# top.net
KiCad netlist of a schematic drawn in Altium Designer
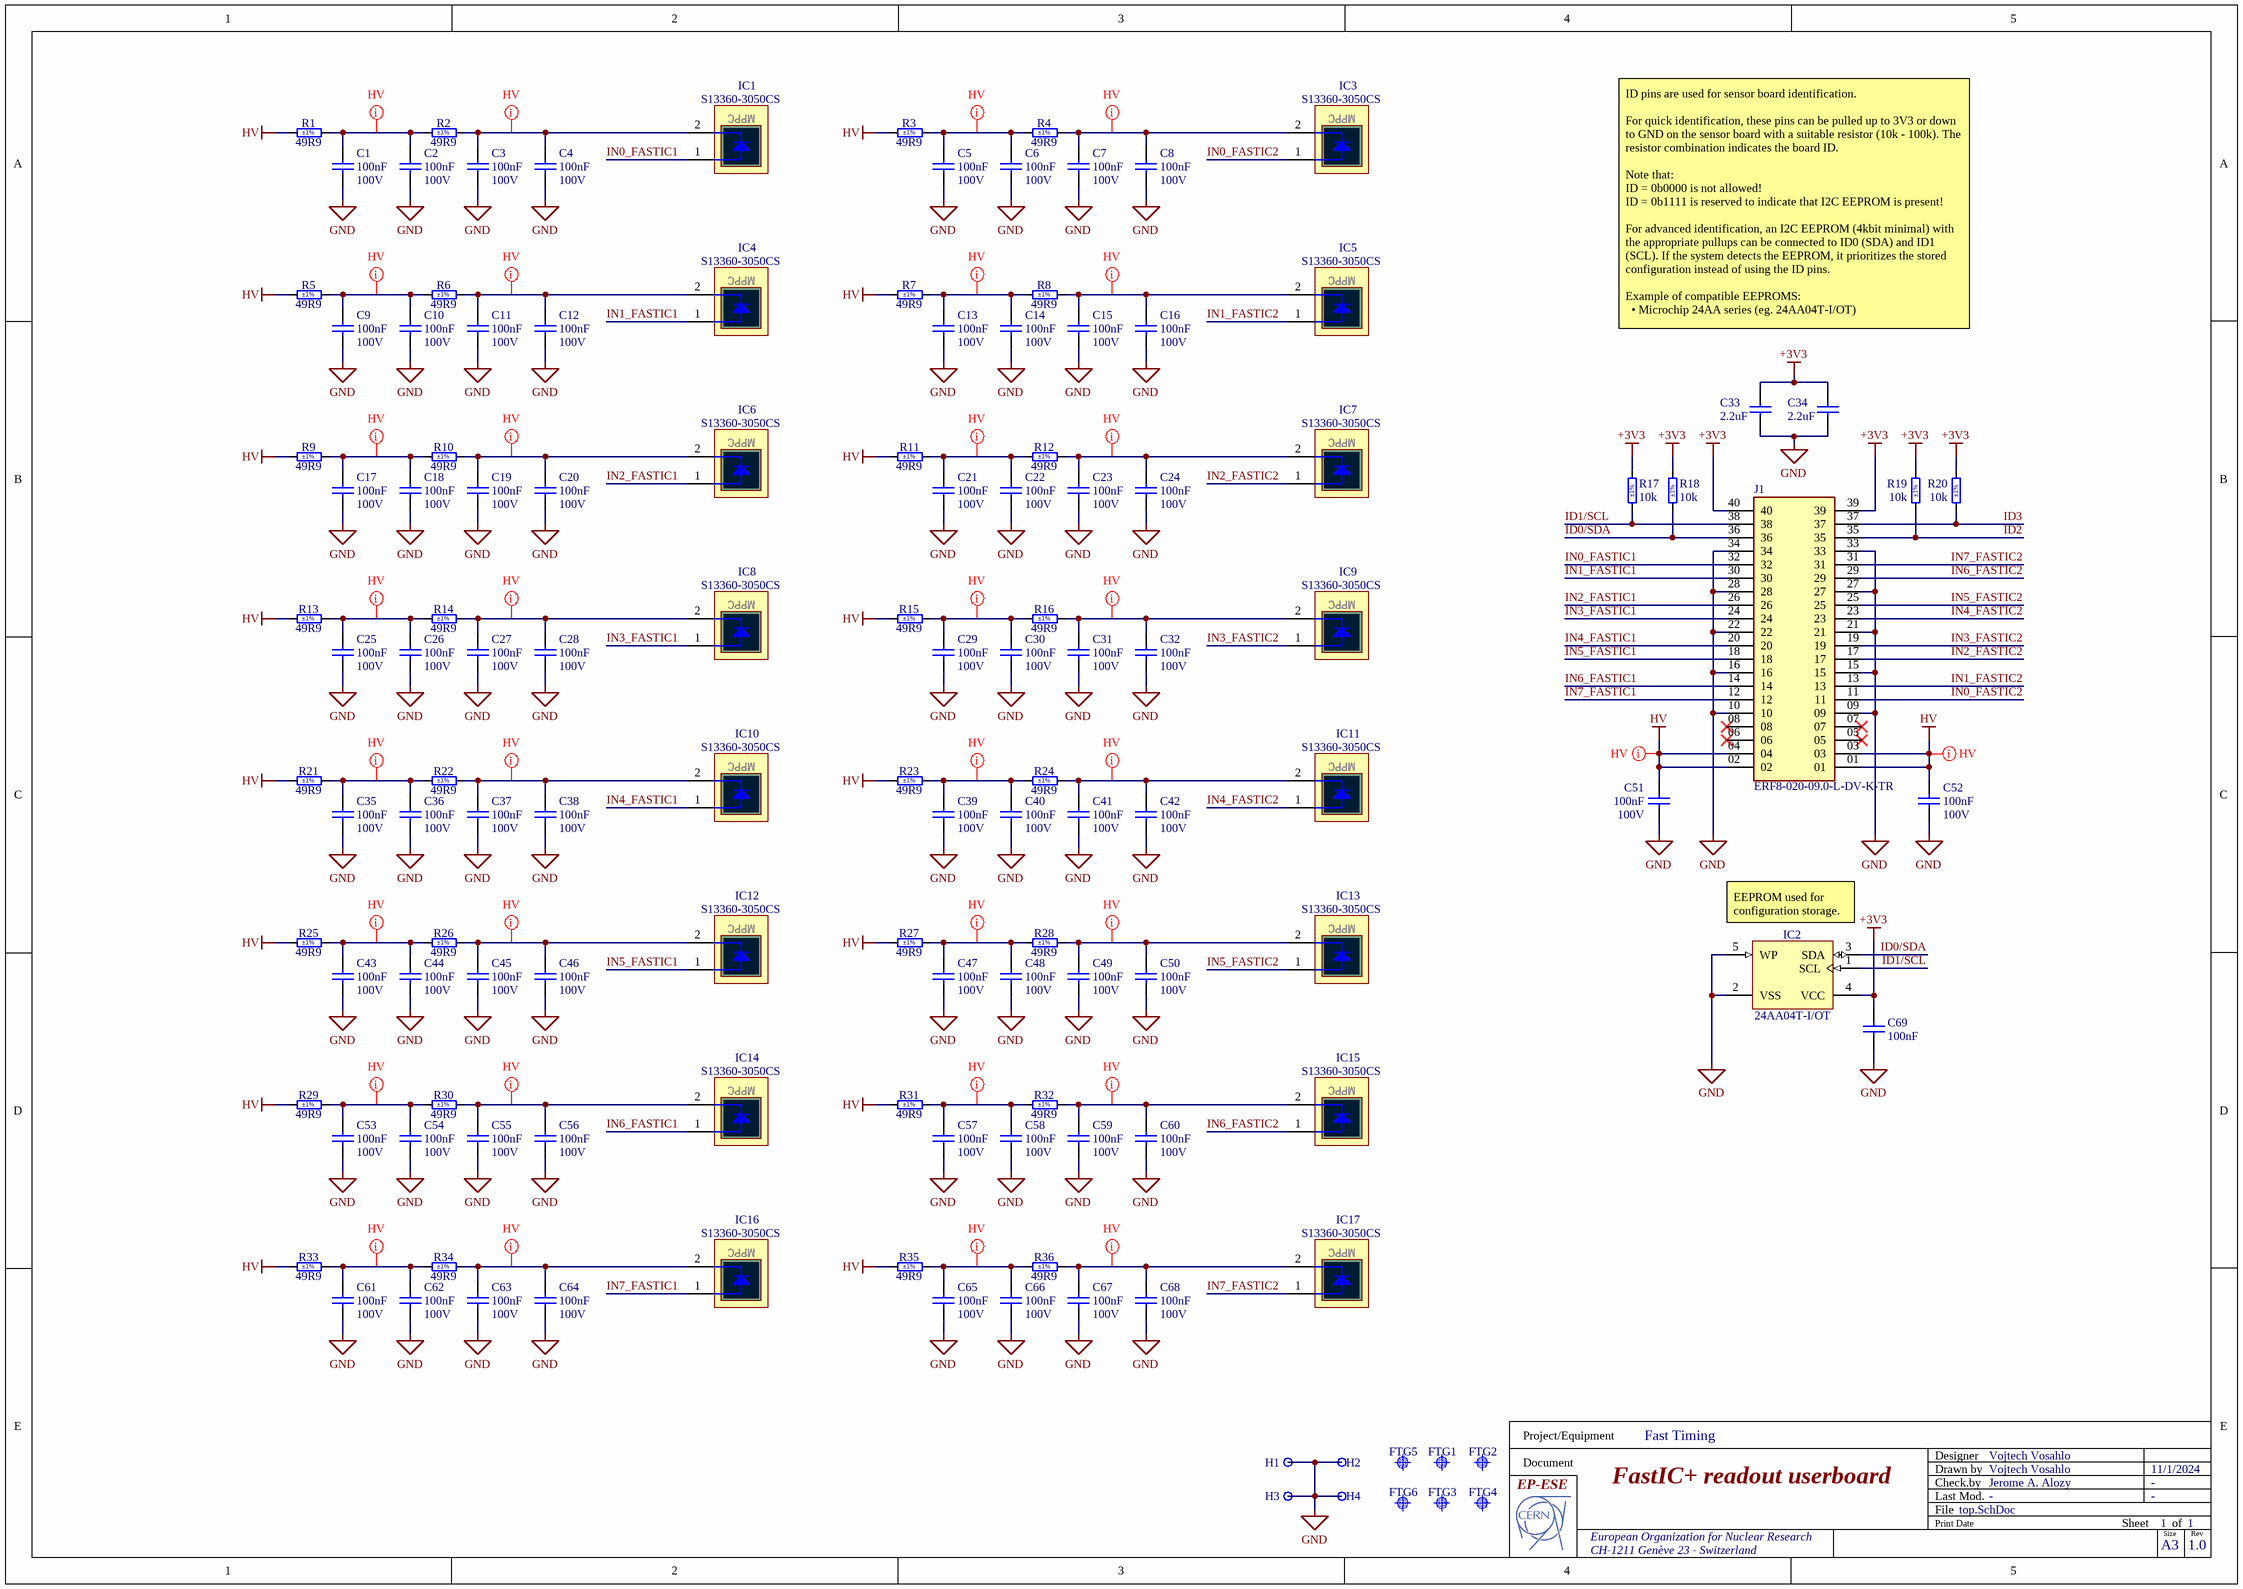
[diagram p0: top.SchDoc]

(export (version "E")
  (design (tool "Eeschema 10.0.6"))
  (components
    (comp (ref "C1")
      (value "100nF")
      (footprint "CAPC1608X90N")
      (description "Non-polarised capacitor")
      (fields
        (field (name "PART NUMBER") "CC0603_100NF_100V_10%_X7R")
        (field (name "VOLTAGE") "100V")
        (field (name "TOLERANCE") "±10%")
        (field (name "AUTHOR") "CERN DEM JLC")
      )
      (libsource (lib "Capacitors") (part "Capacitor - non polarized"))
    )
    (comp (ref "C2")
      (value "100nF")
      (footprint "CAPC1608X90N")
      (description "Non-polarised capacitor")
      (fields
        (field (name "PART NUMBER") "CC0603_100NF_100V_10%_X7R")
        (field (name "VOLTAGE") "100V")
        (field (name "TOLERANCE") "±10%")
        (field (name "AUTHOR") "CERN DEM JLC")
      )
      (libsource (lib "Capacitors") (part "Capacitor - non polarized"))
    )
    (comp (ref "C3")
      (value "100nF")
      (footprint "CAPC1608X90N")
      (description "Non-polarised capacitor")
      (fields
        (field (name "PART NUMBER") "CC0603_100NF_100V_10%_X7R")
        (field (name "VOLTAGE") "100V")
        (field (name "TOLERANCE") "±10%")
        (field (name "AUTHOR") "CERN DEM JLC")
      )
      (libsource (lib "Capacitors") (part "Capacitor - non polarized"))
    )
    (comp (ref "C4")
      (value "100nF")
      (footprint "CAPC1608X90N")
      (description "Non-polarised capacitor")
      (fields
        (field (name "PART NUMBER") "CC0603_100NF_100V_10%_X7R")
        (field (name "VOLTAGE") "100V")
        (field (name "TOLERANCE") "±10%")
        (field (name "AUTHOR") "CERN DEM JLC")
      )
      (libsource (lib "Capacitors") (part "Capacitor - non polarized"))
    )
    (comp (ref "C5")
      (value "100nF")
      (footprint "CAPC1608X90N")
      (description "Non-polarised capacitor")
      (fields
        (field (name "PART NUMBER") "CC0603_100NF_100V_10%_X7R")
        (field (name "VOLTAGE") "100V")
        (field (name "TOLERANCE") "±10%")
        (field (name "AUTHOR") "CERN DEM JLC")
      )
      (libsource (lib "Capacitors") (part "Capacitor - non polarized"))
    )
    (comp (ref "C6")
      (value "100nF")
      (footprint "CAPC1608X90N")
      (description "Non-polarised capacitor")
      (fields
        (field (name "PART NUMBER") "CC0603_100NF_100V_10%_X7R")
        (field (name "VOLTAGE") "100V")
        (field (name "TOLERANCE") "±10%")
        (field (name "AUTHOR") "CERN DEM JLC")
      )
      (libsource (lib "Capacitors") (part "Capacitor - non polarized"))
    )
    (comp (ref "C7")
      (value "100nF")
      (footprint "CAPC1608X90N")
      (description "Non-polarised capacitor")
      (fields
        (field (name "PART NUMBER") "CC0603_100NF_100V_10%_X7R")
        (field (name "VOLTAGE") "100V")
        (field (name "TOLERANCE") "±10%")
        (field (name "AUTHOR") "CERN DEM JLC")
      )
      (libsource (lib "Capacitors") (part "Capacitor - non polarized"))
    )
    (comp (ref "C8")
      (value "100nF")
      (footprint "CAPC1608X90N")
      (description "Non-polarised capacitor")
      (fields
        (field (name "PART NUMBER") "CC0603_100NF_100V_10%_X7R")
        (field (name "VOLTAGE") "100V")
        (field (name "TOLERANCE") "±10%")
        (field (name "AUTHOR") "CERN DEM JLC")
      )
      (libsource (lib "Capacitors") (part "Capacitor - non polarized"))
    )
    (comp (ref "C9")
      (value "100nF")
      (footprint "CAPC1608X90N")
      (description "Non-polarised capacitor")
      (fields
        (field (name "PART NUMBER") "CC0603_100NF_100V_10%_X7R")
        (field (name "VOLTAGE") "100V")
        (field (name "TOLERANCE") "±10%")
        (field (name "AUTHOR") "CERN DEM JLC")
      )
      (libsource (lib "Capacitors") (part "Capacitor - non polarized"))
    )
    (comp (ref "C10")
      (value "100nF")
      (footprint "CAPC1608X90N")
      (description "Non-polarised capacitor")
      (fields
        (field (name "PART NUMBER") "CC0603_100NF_100V_10%_X7R")
        (field (name "VOLTAGE") "100V")
        (field (name "TOLERANCE") "±10%")
        (field (name "AUTHOR") "CERN DEM JLC")
      )
      (libsource (lib "Capacitors") (part "Capacitor - non polarized"))
    )
    (comp (ref "C11")
      (value "100nF")
      (footprint "CAPC1608X90N")
      (description "Non-polarised capacitor")
      (fields
        (field (name "PART NUMBER") "CC0603_100NF_100V_10%_X7R")
        (field (name "VOLTAGE") "100V")
        (field (name "TOLERANCE") "±10%")
        (field (name "AUTHOR") "CERN DEM JLC")
      )
      (libsource (lib "Capacitors") (part "Capacitor - non polarized"))
    )
    (comp (ref "C12")
      (value "100nF")
      (footprint "CAPC1608X90N")
      (description "Non-polarised capacitor")
      (fields
        (field (name "PART NUMBER") "CC0603_100NF_100V_10%_X7R")
        (field (name "VOLTAGE") "100V")
        (field (name "TOLERANCE") "±10%")
        (field (name "AUTHOR") "CERN DEM JLC")
      )
      (libsource (lib "Capacitors") (part "Capacitor - non polarized"))
    )
    (comp (ref "C13")
      (value "100nF")
      (footprint "CAPC1608X90N")
      (description "Non-polarised capacitor")
      (fields
        (field (name "PART NUMBER") "CC0603_100NF_100V_10%_X7R")
        (field (name "VOLTAGE") "100V")
        (field (name "TOLERANCE") "±10%")
        (field (name "AUTHOR") "CERN DEM JLC")
      )
      (libsource (lib "Capacitors") (part "Capacitor - non polarized"))
    )
    (comp (ref "C14")
      (value "100nF")
      (footprint "CAPC1608X90N")
      (description "Non-polarised capacitor")
      (fields
        (field (name "PART NUMBER") "CC0603_100NF_100V_10%_X7R")
        (field (name "VOLTAGE") "100V")
        (field (name "TOLERANCE") "±10%")
        (field (name "AUTHOR") "CERN DEM JLC")
      )
      (libsource (lib "Capacitors") (part "Capacitor - non polarized"))
    )
    (comp (ref "C15")
      (value "100nF")
      (footprint "CAPC1608X90N")
      (description "Non-polarised capacitor")
      (fields
        (field (name "PART NUMBER") "CC0603_100NF_100V_10%_X7R")
        (field (name "VOLTAGE") "100V")
        (field (name "TOLERANCE") "±10%")
        (field (name "AUTHOR") "CERN DEM JLC")
      )
      (libsource (lib "Capacitors") (part "Capacitor - non polarized"))
    )
    (comp (ref "C16")
      (value "100nF")
      (footprint "CAPC1608X90N")
      (description "Non-polarised capacitor")
      (fields
        (field (name "PART NUMBER") "CC0603_100NF_100V_10%_X7R")
        (field (name "VOLTAGE") "100V")
        (field (name "TOLERANCE") "±10%")
        (field (name "AUTHOR") "CERN DEM JLC")
      )
      (libsource (lib "Capacitors") (part "Capacitor - non polarized"))
    )
    (comp (ref "C17")
      (value "100nF")
      (footprint "CAPC1608X90N")
      (description "Non-polarised capacitor")
      (fields
        (field (name "PART NUMBER") "CC0603_100NF_100V_10%_X7R")
        (field (name "VOLTAGE") "100V")
        (field (name "TOLERANCE") "±10%")
        (field (name "AUTHOR") "CERN DEM JLC")
      )
      (libsource (lib "Capacitors") (part "Capacitor - non polarized"))
    )
    (comp (ref "C18")
      (value "100nF")
      (footprint "CAPC1608X90N")
      (description "Non-polarised capacitor")
      (fields
        (field (name "PART NUMBER") "CC0603_100NF_100V_10%_X7R")
        (field (name "VOLTAGE") "100V")
        (field (name "TOLERANCE") "±10%")
        (field (name "AUTHOR") "CERN DEM JLC")
      )
      (libsource (lib "Capacitors") (part "Capacitor - non polarized"))
    )
    (comp (ref "C19")
      (value "100nF")
      (footprint "CAPC1608X90N")
      (description "Non-polarised capacitor")
      (fields
        (field (name "PART NUMBER") "CC0603_100NF_100V_10%_X7R")
        (field (name "VOLTAGE") "100V")
        (field (name "TOLERANCE") "±10%")
        (field (name "AUTHOR") "CERN DEM JLC")
      )
      (libsource (lib "Capacitors") (part "Capacitor - non polarized"))
    )
    (comp (ref "C20")
      (value "100nF")
      (footprint "CAPC1608X90N")
      (description "Non-polarised capacitor")
      (fields
        (field (name "PART NUMBER") "CC0603_100NF_100V_10%_X7R")
        (field (name "VOLTAGE") "100V")
        (field (name "TOLERANCE") "±10%")
        (field (name "AUTHOR") "CERN DEM JLC")
      )
      (libsource (lib "Capacitors") (part "Capacitor - non polarized"))
    )
    (comp (ref "C21")
      (value "100nF")
      (footprint "CAPC1608X90N")
      (description "Non-polarised capacitor")
      (fields
        (field (name "PART NUMBER") "CC0603_100NF_100V_10%_X7R")
        (field (name "VOLTAGE") "100V")
        (field (name "TOLERANCE") "±10%")
        (field (name "AUTHOR") "CERN DEM JLC")
      )
      (libsource (lib "Capacitors") (part "Capacitor - non polarized"))
    )
    (comp (ref "C22")
      (value "100nF")
      (footprint "CAPC1608X90N")
      (description "Non-polarised capacitor")
      (fields
        (field (name "PART NUMBER") "CC0603_100NF_100V_10%_X7R")
        (field (name "VOLTAGE") "100V")
        (field (name "TOLERANCE") "±10%")
        (field (name "AUTHOR") "CERN DEM JLC")
      )
      (libsource (lib "Capacitors") (part "Capacitor - non polarized"))
    )
    (comp (ref "C23")
      (value "100nF")
      (footprint "CAPC1608X90N")
      (description "Non-polarised capacitor")
      (fields
        (field (name "PART NUMBER") "CC0603_100NF_100V_10%_X7R")
        (field (name "VOLTAGE") "100V")
        (field (name "TOLERANCE") "±10%")
        (field (name "AUTHOR") "CERN DEM JLC")
      )
      (libsource (lib "Capacitors") (part "Capacitor - non polarized"))
    )
    (comp (ref "C24")
      (value "100nF")
      (footprint "CAPC1608X90N")
      (description "Non-polarised capacitor")
      (fields
        (field (name "PART NUMBER") "CC0603_100NF_100V_10%_X7R")
        (field (name "VOLTAGE") "100V")
        (field (name "TOLERANCE") "±10%")
        (field (name "AUTHOR") "CERN DEM JLC")
      )
      (libsource (lib "Capacitors") (part "Capacitor - non polarized"))
    )
    (comp (ref "C25")
      (value "100nF")
      (footprint "CAPC1608X90N")
      (description "Non-polarised capacitor")
      (fields
        (field (name "PART NUMBER") "CC0603_100NF_100V_10%_X7R")
        (field (name "VOLTAGE") "100V")
        (field (name "TOLERANCE") "±10%")
        (field (name "AUTHOR") "CERN DEM JLC")
      )
      (libsource (lib "Capacitors") (part "Capacitor - non polarized"))
    )
    (comp (ref "C26")
      (value "100nF")
      (footprint "CAPC1608X90N")
      (description "Non-polarised capacitor")
      (fields
        (field (name "PART NUMBER") "CC0603_100NF_100V_10%_X7R")
        (field (name "VOLTAGE") "100V")
        (field (name "TOLERANCE") "±10%")
        (field (name "AUTHOR") "CERN DEM JLC")
      )
      (libsource (lib "Capacitors") (part "Capacitor - non polarized"))
    )
    (comp (ref "C27")
      (value "100nF")
      (footprint "CAPC1608X90N")
      (description "Non-polarised capacitor")
      (fields
        (field (name "PART NUMBER") "CC0603_100NF_100V_10%_X7R")
        (field (name "VOLTAGE") "100V")
        (field (name "TOLERANCE") "±10%")
        (field (name "AUTHOR") "CERN DEM JLC")
      )
      (libsource (lib "Capacitors") (part "Capacitor - non polarized"))
    )
    (comp (ref "C28")
      (value "100nF")
      (footprint "CAPC1608X90N")
      (description "Non-polarised capacitor")
      (fields
        (field (name "PART NUMBER") "CC0603_100NF_100V_10%_X7R")
        (field (name "VOLTAGE") "100V")
        (field (name "TOLERANCE") "±10%")
        (field (name "AUTHOR") "CERN DEM JLC")
      )
      (libsource (lib "Capacitors") (part "Capacitor - non polarized"))
    )
    (comp (ref "C29")
      (value "100nF")
      (footprint "CAPC1608X90N")
      (description "Non-polarised capacitor")
      (fields
        (field (name "PART NUMBER") "CC0603_100NF_100V_10%_X7R")
        (field (name "VOLTAGE") "100V")
        (field (name "TOLERANCE") "±10%")
        (field (name "AUTHOR") "CERN DEM JLC")
      )
      (libsource (lib "Capacitors") (part "Capacitor - non polarized"))
    )
    (comp (ref "C30")
      (value "100nF")
      (footprint "CAPC1608X90N")
      (description "Non-polarised capacitor")
      (fields
        (field (name "PART NUMBER") "CC0603_100NF_100V_10%_X7R")
        (field (name "VOLTAGE") "100V")
        (field (name "TOLERANCE") "±10%")
        (field (name "AUTHOR") "CERN DEM JLC")
      )
      (libsource (lib "Capacitors") (part "Capacitor - non polarized"))
    )
    (comp (ref "C31")
      (value "100nF")
      (footprint "CAPC1608X90N")
      (description "Non-polarised capacitor")
      (fields
        (field (name "PART NUMBER") "CC0603_100NF_100V_10%_X7R")
        (field (name "VOLTAGE") "100V")
        (field (name "TOLERANCE") "±10%")
        (field (name "AUTHOR") "CERN DEM JLC")
      )
      (libsource (lib "Capacitors") (part "Capacitor - non polarized"))
    )
    (comp (ref "C32")
      (value "100nF")
      (footprint "CAPC1608X90N")
      (description "Non-polarised capacitor")
      (fields
        (field (name "PART NUMBER") "CC0603_100NF_100V_10%_X7R")
        (field (name "VOLTAGE") "100V")
        (field (name "TOLERANCE") "±10%")
        (field (name "AUTHOR") "CERN DEM JLC")
      )
      (libsource (lib "Capacitors") (part "Capacitor - non polarized"))
    )
    (comp (ref "C33")
      (value "2.2uF")
      (footprint "CAPC1608X90N")
      (description "Non-polarised capacitor")
      (fields
        (field (name "PART NUMBER") "CC0603_2.2UF_10V_20%_X7R")
        (field (name "VOLTAGE") "10V")
        (field (name "AUTHOR") "CERN DEM JLC")
      )
      (libsource (lib "Capacitors") (part "Capacitor - non polarized"))
    )
    (comp (ref "C34")
      (value "2.2uF")
      (footprint "CAPC1608X90N")
      (description "Non-polarised capacitor")
      (fields
        (field (name "PART NUMBER") "CC0603_2.2UF_10V_20%_X7R")
        (field (name "VOLTAGE") "10V")
        (field (name "AUTHOR") "CERN DEM JLC")
      )
      (libsource (lib "Capacitors") (part "Capacitor - non polarized"))
    )
    (comp (ref "C35")
      (value "100nF")
      (footprint "CAPC1608X90N")
      (description "Non-polarised capacitor")
      (fields
        (field (name "PART NUMBER") "CC0603_100NF_100V_10%_X7R")
        (field (name "VOLTAGE") "100V")
        (field (name "TOLERANCE") "±10%")
        (field (name "AUTHOR") "CERN DEM JLC")
      )
      (libsource (lib "Capacitors") (part "Capacitor - non polarized"))
    )
    (comp (ref "C36")
      (value "100nF")
      (footprint "CAPC1608X90N")
      (description "Non-polarised capacitor")
      (fields
        (field (name "PART NUMBER") "CC0603_100NF_100V_10%_X7R")
        (field (name "VOLTAGE") "100V")
        (field (name "TOLERANCE") "±10%")
        (field (name "AUTHOR") "CERN DEM JLC")
      )
      (libsource (lib "Capacitors") (part "Capacitor - non polarized"))
    )
    (comp (ref "C37")
      (value "100nF")
      (footprint "CAPC1608X90N")
      (description "Non-polarised capacitor")
      (fields
        (field (name "PART NUMBER") "CC0603_100NF_100V_10%_X7R")
        (field (name "VOLTAGE") "100V")
        (field (name "TOLERANCE") "±10%")
        (field (name "AUTHOR") "CERN DEM JLC")
      )
      (libsource (lib "Capacitors") (part "Capacitor - non polarized"))
    )
    (comp (ref "C38")
      (value "100nF")
      (footprint "CAPC1608X90N")
      (description "Non-polarised capacitor")
      (fields
        (field (name "PART NUMBER") "CC0603_100NF_100V_10%_X7R")
        (field (name "VOLTAGE") "100V")
        (field (name "TOLERANCE") "±10%")
        (field (name "AUTHOR") "CERN DEM JLC")
      )
      (libsource (lib "Capacitors") (part "Capacitor - non polarized"))
    )
    (comp (ref "C39")
      (value "100nF")
      (footprint "CAPC1608X90N")
      (description "Non-polarised capacitor")
      (fields
        (field (name "PART NUMBER") "CC0603_100NF_100V_10%_X7R")
        (field (name "VOLTAGE") "100V")
        (field (name "TOLERANCE") "±10%")
        (field (name "AUTHOR") "CERN DEM JLC")
      )
      (libsource (lib "Capacitors") (part "Capacitor - non polarized"))
    )
    (comp (ref "C40")
      (value "100nF")
      (footprint "CAPC1608X90N")
      (description "Non-polarised capacitor")
      (fields
        (field (name "PART NUMBER") "CC0603_100NF_100V_10%_X7R")
        (field (name "VOLTAGE") "100V")
        (field (name "TOLERANCE") "±10%")
        (field (name "AUTHOR") "CERN DEM JLC")
      )
      (libsource (lib "Capacitors") (part "Capacitor - non polarized"))
    )
    (comp (ref "C41")
      (value "100nF")
      (footprint "CAPC1608X90N")
      (description "Non-polarised capacitor")
      (fields
        (field (name "PART NUMBER") "CC0603_100NF_100V_10%_X7R")
        (field (name "VOLTAGE") "100V")
        (field (name "TOLERANCE") "±10%")
        (field (name "AUTHOR") "CERN DEM JLC")
      )
      (libsource (lib "Capacitors") (part "Capacitor - non polarized"))
    )
    (comp (ref "C42")
      (value "100nF")
      (footprint "CAPC1608X90N")
      (description "Non-polarised capacitor")
      (fields
        (field (name "PART NUMBER") "CC0603_100NF_100V_10%_X7R")
        (field (name "VOLTAGE") "100V")
        (field (name "TOLERANCE") "±10%")
        (field (name "AUTHOR") "CERN DEM JLC")
      )
      (libsource (lib "Capacitors") (part "Capacitor - non polarized"))
    )
    (comp (ref "C43")
      (value "100nF")
      (footprint "CAPC1608X90N")
      (description "Non-polarised capacitor")
      (fields
        (field (name "PART NUMBER") "CC0603_100NF_100V_10%_X7R")
        (field (name "VOLTAGE") "100V")
        (field (name "TOLERANCE") "±10%")
        (field (name "AUTHOR") "CERN DEM JLC")
      )
      (libsource (lib "Capacitors") (part "Capacitor - non polarized"))
    )
    (comp (ref "C44")
      (value "100nF")
      (footprint "CAPC1608X90N")
      (description "Non-polarised capacitor")
      (fields
        (field (name "PART NUMBER") "CC0603_100NF_100V_10%_X7R")
        (field (name "VOLTAGE") "100V")
        (field (name "TOLERANCE") "±10%")
        (field (name "AUTHOR") "CERN DEM JLC")
      )
      (libsource (lib "Capacitors") (part "Capacitor - non polarized"))
    )
    (comp (ref "C45")
      (value "100nF")
      (footprint "CAPC1608X90N")
      (description "Non-polarised capacitor")
      (fields
        (field (name "PART NUMBER") "CC0603_100NF_100V_10%_X7R")
        (field (name "VOLTAGE") "100V")
        (field (name "TOLERANCE") "±10%")
        (field (name "AUTHOR") "CERN DEM JLC")
      )
      (libsource (lib "Capacitors") (part "Capacitor - non polarized"))
    )
    (comp (ref "C46")
      (value "100nF")
      (footprint "CAPC1608X90N")
      (description "Non-polarised capacitor")
      (fields
        (field (name "PART NUMBER") "CC0603_100NF_100V_10%_X7R")
        (field (name "VOLTAGE") "100V")
        (field (name "TOLERANCE") "±10%")
        (field (name "AUTHOR") "CERN DEM JLC")
      )
      (libsource (lib "Capacitors") (part "Capacitor - non polarized"))
    )
    (comp (ref "C47")
      (value "100nF")
      (footprint "CAPC1608X90N")
      (description "Non-polarised capacitor")
      (fields
        (field (name "PART NUMBER") "CC0603_100NF_100V_10%_X7R")
        (field (name "VOLTAGE") "100V")
        (field (name "TOLERANCE") "±10%")
        (field (name "AUTHOR") "CERN DEM JLC")
      )
      (libsource (lib "Capacitors") (part "Capacitor - non polarized"))
    )
    (comp (ref "C48")
      (value "100nF")
      (footprint "CAPC1608X90N")
      (description "Non-polarised capacitor")
      (fields
        (field (name "PART NUMBER") "CC0603_100NF_100V_10%_X7R")
        (field (name "VOLTAGE") "100V")
        (field (name "TOLERANCE") "±10%")
        (field (name "AUTHOR") "CERN DEM JLC")
      )
      (libsource (lib "Capacitors") (part "Capacitor - non polarized"))
    )
    (comp (ref "C49")
      (value "100nF")
      (footprint "CAPC1608X90N")
      (description "Non-polarised capacitor")
      (fields
        (field (name "PART NUMBER") "CC0603_100NF_100V_10%_X7R")
        (field (name "VOLTAGE") "100V")
        (field (name "TOLERANCE") "±10%")
        (field (name "AUTHOR") "CERN DEM JLC")
      )
      (libsource (lib "Capacitors") (part "Capacitor - non polarized"))
    )
    (comp (ref "C50")
      (value "100nF")
      (footprint "CAPC1608X90N")
      (description "Non-polarised capacitor")
      (fields
        (field (name "PART NUMBER") "CC0603_100NF_100V_10%_X7R")
        (field (name "VOLTAGE") "100V")
        (field (name "TOLERANCE") "±10%")
        (field (name "AUTHOR") "CERN DEM JLC")
      )
      (libsource (lib "Capacitors") (part "Capacitor - non polarized"))
    )
    (comp (ref "C51")
      (value "100nF")
      (footprint "CAPC1608X90N")
      (description "Non-polarised capacitor")
      (fields
        (field (name "PART NUMBER") "CC0603_100NF_100V_10%_X7R")
        (field (name "VOLTAGE") "100V")
        (field (name "TOLERANCE") "±10%")
        (field (name "AUTHOR") "CERN DEM JLC")
      )
      (libsource (lib "Capacitors") (part "Capacitor - non polarized"))
    )
    (comp (ref "C52")
      (value "100nF")
      (footprint "CAPC1608X90N")
      (description "Non-polarised capacitor")
      (fields
        (field (name "PART NUMBER") "CC0603_100NF_100V_10%_X7R")
        (field (name "VOLTAGE") "100V")
        (field (name "TOLERANCE") "±10%")
        (field (name "AUTHOR") "CERN DEM JLC")
      )
      (libsource (lib "Capacitors") (part "Capacitor - non polarized"))
    )
    (comp (ref "C53")
      (value "100nF")
      (footprint "CAPC1608X90N")
      (description "Non-polarised capacitor")
      (fields
        (field (name "PART NUMBER") "CC0603_100NF_100V_10%_X7R")
        (field (name "VOLTAGE") "100V")
        (field (name "TOLERANCE") "±10%")
        (field (name "AUTHOR") "CERN DEM JLC")
      )
      (libsource (lib "Capacitors") (part "Capacitor - non polarized"))
    )
    (comp (ref "C54")
      (value "100nF")
      (footprint "CAPC1608X90N")
      (description "Non-polarised capacitor")
      (fields
        (field (name "PART NUMBER") "CC0603_100NF_100V_10%_X7R")
        (field (name "VOLTAGE") "100V")
        (field (name "TOLERANCE") "±10%")
        (field (name "AUTHOR") "CERN DEM JLC")
      )
      (libsource (lib "Capacitors") (part "Capacitor - non polarized"))
    )
    (comp (ref "C55")
      (value "100nF")
      (footprint "CAPC1608X90N")
      (description "Non-polarised capacitor")
      (fields
        (field (name "PART NUMBER") "CC0603_100NF_100V_10%_X7R")
        (field (name "VOLTAGE") "100V")
        (field (name "TOLERANCE") "±10%")
        (field (name "AUTHOR") "CERN DEM JLC")
      )
      (libsource (lib "Capacitors") (part "Capacitor - non polarized"))
    )
    (comp (ref "C56")
      (value "100nF")
      (footprint "CAPC1608X90N")
      (description "Non-polarised capacitor")
      (fields
        (field (name "PART NUMBER") "CC0603_100NF_100V_10%_X7R")
        (field (name "VOLTAGE") "100V")
        (field (name "TOLERANCE") "±10%")
        (field (name "AUTHOR") "CERN DEM JLC")
      )
      (libsource (lib "Capacitors") (part "Capacitor - non polarized"))
    )
    (comp (ref "C57")
      (value "100nF")
      (footprint "CAPC1608X90N")
      (description "Non-polarised capacitor")
      (fields
        (field (name "PART NUMBER") "CC0603_100NF_100V_10%_X7R")
        (field (name "VOLTAGE") "100V")
        (field (name "TOLERANCE") "±10%")
        (field (name "AUTHOR") "CERN DEM JLC")
      )
      (libsource (lib "Capacitors") (part "Capacitor - non polarized"))
    )
    (comp (ref "C58")
      (value "100nF")
      (footprint "CAPC1608X90N")
      (description "Non-polarised capacitor")
      (fields
        (field (name "PART NUMBER") "CC0603_100NF_100V_10%_X7R")
        (field (name "VOLTAGE") "100V")
        (field (name "TOLERANCE") "±10%")
        (field (name "AUTHOR") "CERN DEM JLC")
      )
      (libsource (lib "Capacitors") (part "Capacitor - non polarized"))
    )
    (comp (ref "C59")
      (value "100nF")
      (footprint "CAPC1608X90N")
      (description "Non-polarised capacitor")
      (fields
        (field (name "PART NUMBER") "CC0603_100NF_100V_10%_X7R")
        (field (name "VOLTAGE") "100V")
        (field (name "TOLERANCE") "±10%")
        (field (name "AUTHOR") "CERN DEM JLC")
      )
      (libsource (lib "Capacitors") (part "Capacitor - non polarized"))
    )
    (comp (ref "C60")
      (value "100nF")
      (footprint "CAPC1608X90N")
      (description "Non-polarised capacitor")
      (fields
        (field (name "PART NUMBER") "CC0603_100NF_100V_10%_X7R")
        (field (name "VOLTAGE") "100V")
        (field (name "TOLERANCE") "±10%")
        (field (name "AUTHOR") "CERN DEM JLC")
      )
      (libsource (lib "Capacitors") (part "Capacitor - non polarized"))
    )
    (comp (ref "C61")
      (value "100nF")
      (footprint "CAPC1608X90N")
      (description "Non-polarised capacitor")
      (fields
        (field (name "PART NUMBER") "CC0603_100NF_100V_10%_X7R")
        (field (name "VOLTAGE") "100V")
        (field (name "TOLERANCE") "±10%")
        (field (name "AUTHOR") "CERN DEM JLC")
      )
      (libsource (lib "Capacitors") (part "Capacitor - non polarized"))
    )
    (comp (ref "C62")
      (value "100nF")
      (footprint "CAPC1608X90N")
      (description "Non-polarised capacitor")
      (fields
        (field (name "PART NUMBER") "CC0603_100NF_100V_10%_X7R")
        (field (name "VOLTAGE") "100V")
        (field (name "TOLERANCE") "±10%")
        (field (name "AUTHOR") "CERN DEM JLC")
      )
      (libsource (lib "Capacitors") (part "Capacitor - non polarized"))
    )
    (comp (ref "C63")
      (value "100nF")
      (footprint "CAPC1608X90N")
      (description "Non-polarised capacitor")
      (fields
        (field (name "PART NUMBER") "CC0603_100NF_100V_10%_X7R")
        (field (name "VOLTAGE") "100V")
        (field (name "TOLERANCE") "±10%")
        (field (name "AUTHOR") "CERN DEM JLC")
      )
      (libsource (lib "Capacitors") (part "Capacitor - non polarized"))
    )
    (comp (ref "C64")
      (value "100nF")
      (footprint "CAPC1608X90N")
      (description "Non-polarised capacitor")
      (fields
        (field (name "PART NUMBER") "CC0603_100NF_100V_10%_X7R")
        (field (name "VOLTAGE") "100V")
        (field (name "TOLERANCE") "±10%")
        (field (name "AUTHOR") "CERN DEM JLC")
      )
      (libsource (lib "Capacitors") (part "Capacitor - non polarized"))
    )
    (comp (ref "C65")
      (value "100nF")
      (footprint "CAPC1608X90N")
      (description "Non-polarised capacitor")
      (fields
        (field (name "PART NUMBER") "CC0603_100NF_100V_10%_X7R")
        (field (name "VOLTAGE") "100V")
        (field (name "TOLERANCE") "±10%")
        (field (name "AUTHOR") "CERN DEM JLC")
      )
      (libsource (lib "Capacitors") (part "Capacitor - non polarized"))
    )
    (comp (ref "C66")
      (value "100nF")
      (footprint "CAPC1608X90N")
      (description "Non-polarised capacitor")
      (fields
        (field (name "PART NUMBER") "CC0603_100NF_100V_10%_X7R")
        (field (name "VOLTAGE") "100V")
        (field (name "TOLERANCE") "±10%")
        (field (name "AUTHOR") "CERN DEM JLC")
      )
      (libsource (lib "Capacitors") (part "Capacitor - non polarized"))
    )
    (comp (ref "C67")
      (value "100nF")
      (footprint "CAPC1608X90N")
      (description "Non-polarised capacitor")
      (fields
        (field (name "PART NUMBER") "CC0603_100NF_100V_10%_X7R")
        (field (name "VOLTAGE") "100V")
        (field (name "TOLERANCE") "±10%")
        (field (name "AUTHOR") "CERN DEM JLC")
      )
      (libsource (lib "Capacitors") (part "Capacitor - non polarized"))
    )
    (comp (ref "C68")
      (value "100nF")
      (footprint "CAPC1608X90N")
      (description "Non-polarised capacitor")
      (fields
        (field (name "PART NUMBER") "CC0603_100NF_100V_10%_X7R")
        (field (name "VOLTAGE") "100V")
        (field (name "TOLERANCE") "±10%")
        (field (name "AUTHOR") "CERN DEM JLC")
      )
      (libsource (lib "Capacitors") (part "Capacitor - non polarized"))
    )
    (comp (ref "C69")
      (value "100nF")
      (footprint "CAPC1608X90N")
      (description "Non-polarised capacitor")
      (fields
        (field (name "PART NUMBER") "CC0603_100NF_100V_10%_X7R")
        (field (name "VOLTAGE") "100V")
        (field (name "AUTHOR") "CERN DEM JLC")
      )
      (libsource (lib "Capacitors") (part "Capacitor - non polarized"))
    )
    (comp (ref "FTG1")
      (value "Use only in PCB")
      (footprint "FIDUCIAL_TOP_C100-200")
      (description "Fiducial Target")
      (fields (field (name "PART NUMBER") "FIDUCIAL_TARGET_C100-200") (field (name "AUTHOR") "CERN DEM JLC"))
      (libsource (lib "Eletro-mechanical") (part "Fiducial Target"))
    )
    (comp (ref "FTG2")
      (value "Use only in PCB")
      (footprint "FIDUCIAL_TOP_C100-200")
      (description "Fiducial Target")
      (fields (field (name "PART NUMBER") "FIDUCIAL_TARGET_C100-200") (field (name "AUTHOR") "CERN DEM JLC"))
      (libsource (lib "Eletro-mechanical") (part "Fiducial Target"))
    )
    (comp (ref "FTG3")
      (value "Use only in PCB")
      (footprint "FIDUCIAL_TOP_C100-200")
      (description "Fiducial Target")
      (fields (field (name "PART NUMBER") "FIDUCIAL_TARGET_C100-200") (field (name "AUTHOR") "CERN DEM JLC"))
      (libsource (lib "Eletro-mechanical") (part "Fiducial Target"))
    )
    (comp (ref "FTG4")
      (value "Use only in PCB")
      (footprint "FIDUCIAL_TOP_C100-200")
      (description "Fiducial Target")
      (fields (field (name "PART NUMBER") "FIDUCIAL_TARGET_C100-200") (field (name "AUTHOR") "CERN DEM JLC"))
      (libsource (lib "Eletro-mechanical") (part "Fiducial Target"))
    )
    (comp (ref "FTG5")
      (value "Use only in PCB")
      (footprint "FIDUCIAL_TOP_C100-200")
      (description "Fiducial Target")
      (fields (field (name "PART NUMBER") "FIDUCIAL_TARGET_C100-200") (field (name "AUTHOR") "CERN DEM JLC"))
      (libsource (lib "Eletro-mechanical") (part "Fiducial Target"))
    )
    (comp (ref "FTG6")
      (value "Use only in PCB")
      (footprint "FIDUCIAL_TOP_C100-200")
      (description "Fiducial Target")
      (fields (field (name "PART NUMBER") "FIDUCIAL_TARGET_C100-200") (field (name "AUTHOR") "CERN DEM JLC"))
      (libsource (lib "Eletro-mechanical") (part "Fiducial Target"))
    )
    (comp (ref "H1")
      (value "Plated Hole")
      (footprint "MTG240_400")
      (description "Single Terminal Socket")
      (fields (field (name "PART NUMBER") "PLATED_HOLE2.4_PAD4.0") (field (name "AUTHOR") "CERN DEM JMW"))
      (libsource (lib "Eletro-mechanical") (part "Single Terminal Socket"))
    )
    (comp (ref "H2")
      (value "Plated Hole")
      (footprint "MTG240_400")
      (description "Single Terminal Socket")
      (fields (field (name "PART NUMBER") "PLATED_HOLE2.4_PAD4.0") (field (name "AUTHOR") "CERN DEM JMW"))
      (libsource (lib "Eletro-mechanical") (part "Single Terminal Socket"))
    )
    (comp (ref "H3")
      (value "Plated Hole")
      (footprint "MTG240_400")
      (description "Single Terminal Socket")
      (fields (field (name "PART NUMBER") "PLATED_HOLE2.4_PAD4.0") (field (name "AUTHOR") "CERN DEM JMW"))
      (libsource (lib "Eletro-mechanical") (part "Single Terminal Socket"))
    )
    (comp (ref "H4")
      (value "Plated Hole")
      (footprint "MTG240_400")
      (description "Single Terminal Socket")
      (fields (field (name "PART NUMBER") "PLATED_HOLE2.4_PAD4.0") (field (name "AUTHOR") "CERN DEM JMW"))
      (libsource (lib "Eletro-mechanical") (part "Single Terminal Socket"))
    )
    (comp (ref "IC1")
      (value "S13360-3050CS")
      (footprint "HAMAMATSU_S13360-3050CS")
      (description "Single Element MPPC (Multi-Pixel Photon Counter)")
      (fields (field (name "MANUFACTURER") "HAMAMATSU") (field (name "AUTHOR") "CERN DEM BC"))
      (libsource (lib "ICs And Semiconductors") (part "MPPC-Single Element"))
    )
    (comp (ref "IC2")
      (value "24AA04T-I/OT")
      (footprint "SOT95P280X145-5N")
      (description "1.7V-5.5V, 16K I2C Serial EEPROM")
      (fields
        (field (name "MANUFACTURER") "MICROCHIP TECHNOLOGY")
        (field (name "MANUFACTURER PART NUMBER") "24AA16T-E/OT")
        (field (name "AUTHOR") "CERN DEM BC")
      )
      (libsource (lib "ICs And Semiconductors") (part "24AA16T-X/OT"))
    )
    (comp (ref "IC3")
      (value "S13360-3050CS")
      (footprint "HAMAMATSU_S13360-3050CS")
      (description "Single Element MPPC (Multi-Pixel Photon Counter)")
      (fields (field (name "MANUFACTURER") "HAMAMATSU") (field (name "AUTHOR") "CERN DEM BC"))
      (libsource (lib "ICs And Semiconductors") (part "MPPC-Single Element"))
    )
    (comp (ref "IC4")
      (value "S13360-3050CS")
      (footprint "HAMAMATSU_S13360-3050CS")
      (description "Single Element MPPC (Multi-Pixel Photon Counter)")
      (fields (field (name "MANUFACTURER") "HAMAMATSU") (field (name "AUTHOR") "CERN DEM BC"))
      (libsource (lib "ICs And Semiconductors") (part "MPPC-Single Element"))
    )
    (comp (ref "IC5")
      (value "S13360-3050CS")
      (footprint "HAMAMATSU_S13360-3050CS")
      (description "Single Element MPPC (Multi-Pixel Photon Counter)")
      (fields (field (name "MANUFACTURER") "HAMAMATSU") (field (name "AUTHOR") "CERN DEM BC"))
      (libsource (lib "ICs And Semiconductors") (part "MPPC-Single Element"))
    )
    (comp (ref "IC6")
      (value "S13360-3050CS")
      (footprint "HAMAMATSU_S13360-3050CS")
      (description "Single Element MPPC (Multi-Pixel Photon Counter)")
      (fields (field (name "MANUFACTURER") "HAMAMATSU") (field (name "AUTHOR") "CERN DEM BC"))
      (libsource (lib "ICs And Semiconductors") (part "MPPC-Single Element"))
    )
    (comp (ref "IC7")
      (value "S13360-3050CS")
      (footprint "HAMAMATSU_S13360-3050CS")
      (description "Single Element MPPC (Multi-Pixel Photon Counter)")
      (fields (field (name "MANUFACTURER") "HAMAMATSU") (field (name "AUTHOR") "CERN DEM BC"))
      (libsource (lib "ICs And Semiconductors") (part "MPPC-Single Element"))
    )
    (comp (ref "IC8")
      (value "S13360-3050CS")
      (footprint "HAMAMATSU_S13360-3050CS")
      (description "Single Element MPPC (Multi-Pixel Photon Counter)")
      (fields (field (name "MANUFACTURER") "HAMAMATSU") (field (name "AUTHOR") "CERN DEM BC"))
      (libsource (lib "ICs And Semiconductors") (part "MPPC-Single Element"))
    )
    (comp (ref "IC9")
      (value "S13360-3050CS")
      (footprint "HAMAMATSU_S13360-3050CS")
      (description "Single Element MPPC (Multi-Pixel Photon Counter)")
      (fields (field (name "MANUFACTURER") "HAMAMATSU") (field (name "AUTHOR") "CERN DEM BC"))
      (libsource (lib "ICs And Semiconductors") (part "MPPC-Single Element"))
    )
    (comp (ref "IC10")
      (value "S13360-3050CS")
      (footprint "HAMAMATSU_S13360-3050CS")
      (description "Single Element MPPC (Multi-Pixel Photon Counter)")
      (fields (field (name "MANUFACTURER") "HAMAMATSU") (field (name "AUTHOR") "CERN DEM BC"))
      (libsource (lib "ICs And Semiconductors") (part "MPPC-Single Element"))
    )
    (comp (ref "IC11")
      (value "S13360-3050CS")
      (footprint "HAMAMATSU_S13360-3050CS")
      (description "Single Element MPPC (Multi-Pixel Photon Counter)")
      (fields (field (name "MANUFACTURER") "HAMAMATSU") (field (name "AUTHOR") "CERN DEM BC"))
      (libsource (lib "ICs And Semiconductors") (part "MPPC-Single Element"))
    )
    (comp (ref "IC12")
      (value "S13360-3050CS")
      (footprint "HAMAMATSU_S13360-3050CS")
      (description "Single Element MPPC (Multi-Pixel Photon Counter)")
      (fields (field (name "MANUFACTURER") "HAMAMATSU") (field (name "AUTHOR") "CERN DEM BC"))
      (libsource (lib "ICs And Semiconductors") (part "MPPC-Single Element"))
    )
    (comp (ref "IC13")
      (value "S13360-3050CS")
      (footprint "HAMAMATSU_S13360-3050CS")
      (description "Single Element MPPC (Multi-Pixel Photon Counter)")
      (fields (field (name "MANUFACTURER") "HAMAMATSU") (field (name "AUTHOR") "CERN DEM BC"))
      (libsource (lib "ICs And Semiconductors") (part "MPPC-Single Element"))
    )
    (comp (ref "IC14")
      (value "S13360-3050CS")
      (footprint "HAMAMATSU_S13360-3050CS")
      (description "Single Element MPPC (Multi-Pixel Photon Counter)")
      (fields (field (name "MANUFACTURER") "HAMAMATSU") (field (name "AUTHOR") "CERN DEM BC"))
      (libsource (lib "ICs And Semiconductors") (part "MPPC-Single Element"))
    )
    (comp (ref "IC15")
      (value "S13360-3050CS")
      (footprint "HAMAMATSU_S13360-3050CS")
      (description "Single Element MPPC (Multi-Pixel Photon Counter)")
      (fields (field (name "MANUFACTURER") "HAMAMATSU") (field (name "AUTHOR") "CERN DEM BC"))
      (libsource (lib "ICs And Semiconductors") (part "MPPC-Single Element"))
    )
    (comp (ref "IC16")
      (value "S13360-3050CS")
      (footprint "HAMAMATSU_S13360-3050CS")
      (description "Single Element MPPC (Multi-Pixel Photon Counter)")
      (fields (field (name "MANUFACTURER") "HAMAMATSU") (field (name "AUTHOR") "CERN DEM BC"))
      (libsource (lib "ICs And Semiconductors") (part "MPPC-Single Element"))
    )
    (comp (ref "IC17")
      (value "S13360-3050CS")
      (footprint "HAMAMATSU_S13360-3050CS")
      (description "Single Element MPPC (Multi-Pixel Photon Counter)")
      (fields (field (name "MANUFACTURER") "HAMAMATSU") (field (name "AUTHOR") "CERN DEM BC"))
      (libsource (lib "ICs And Semiconductors") (part "MPPC-Single Element"))
    )
    (comp (ref "J1")
      (value "ERF8-020-09.0-L-DV-K-TR")
      (footprint "SAMTEC_ERF8-020-09.0-L-DV-K-TR")
      (libsource (lib "ERF8-020-09.0-L-DV-K-TR") (part "ERF8-020-09.0-L-DV-K-TR"))
    )
    (comp (ref "R1")
      (value "49R9")
      (footprint "RESC1608X55N")
      (description "Resistor - 1%")
      (fields
        (field (name "TOLERANCE") "±1%")
        (field (name "PART NUMBER") "R0603_49R9_1%_0.1W_100PPM")
        (field (name "POWER") "0.1W")
        (field (name "AUTHOR") "CERN DEM JLC")
      )
      (libsource (lib "Resistors") (part "Resistor - 1%"))
    )
    (comp (ref "R2")
      (value "49R9")
      (footprint "RESC1608X55N")
      (description "Resistor - 1%")
      (fields
        (field (name "TOLERANCE") "±1%")
        (field (name "PART NUMBER") "R0603_49R9_1%_0.1W_100PPM")
        (field (name "POWER") "0.1W")
        (field (name "AUTHOR") "CERN DEM JLC")
      )
      (libsource (lib "Resistors") (part "Resistor - 1%"))
    )
    (comp (ref "R3")
      (value "49R9")
      (footprint "RESC1608X55N")
      (description "Resistor - 1%")
      (fields
        (field (name "TOLERANCE") "±1%")
        (field (name "PART NUMBER") "R0603_49R9_1%_0.1W_100PPM")
        (field (name "POWER") "0.1W")
        (field (name "AUTHOR") "CERN DEM JLC")
      )
      (libsource (lib "Resistors") (part "Resistor - 1%"))
    )
    (comp (ref "R4")
      (value "49R9")
      (footprint "RESC1608X55N")
      (description "Resistor - 1%")
      (fields
        (field (name "TOLERANCE") "±1%")
        (field (name "PART NUMBER") "R0603_49R9_1%_0.1W_100PPM")
        (field (name "POWER") "0.1W")
        (field (name "AUTHOR") "CERN DEM JLC")
      )
      (libsource (lib "Resistors") (part "Resistor - 1%"))
    )
    (comp (ref "R5")
      (value "49R9")
      (footprint "RESC1608X55N")
      (description "Resistor - 1%")
      (fields
        (field (name "TOLERANCE") "±1%")
        (field (name "PART NUMBER") "R0603_49R9_1%_0.1W_100PPM")
        (field (name "POWER") "0.1W")
        (field (name "AUTHOR") "CERN DEM JLC")
      )
      (libsource (lib "Resistors") (part "Resistor - 1%"))
    )
    (comp (ref "R6")
      (value "49R9")
      (footprint "RESC1608X55N")
      (description "Resistor - 1%")
      (fields
        (field (name "TOLERANCE") "±1%")
        (field (name "PART NUMBER") "R0603_49R9_1%_0.1W_100PPM")
        (field (name "POWER") "0.1W")
        (field (name "AUTHOR") "CERN DEM JLC")
      )
      (libsource (lib "Resistors") (part "Resistor - 1%"))
    )
    (comp (ref "R7")
      (value "49R9")
      (footprint "RESC1608X55N")
      (description "Resistor - 1%")
      (fields
        (field (name "TOLERANCE") "±1%")
        (field (name "PART NUMBER") "R0603_49R9_1%_0.1W_100PPM")
        (field (name "POWER") "0.1W")
        (field (name "AUTHOR") "CERN DEM JLC")
      )
      (libsource (lib "Resistors") (part "Resistor - 1%"))
    )
    (comp (ref "R8")
      (value "49R9")
      (footprint "RESC1608X55N")
      (description "Resistor - 1%")
      (fields
        (field (name "TOLERANCE") "±1%")
        (field (name "PART NUMBER") "R0603_49R9_1%_0.1W_100PPM")
        (field (name "POWER") "0.1W")
        (field (name "AUTHOR") "CERN DEM JLC")
      )
      (libsource (lib "Resistors") (part "Resistor - 1%"))
    )
    (comp (ref "R9")
      (value "49R9")
      (footprint "RESC1608X55N")
      (description "Resistor - 1%")
      (fields
        (field (name "TOLERANCE") "±1%")
        (field (name "PART NUMBER") "R0603_49R9_1%_0.1W_100PPM")
        (field (name "POWER") "0.1W")
        (field (name "AUTHOR") "CERN DEM JLC")
      )
      (libsource (lib "Resistors") (part "Resistor - 1%"))
    )
    (comp (ref "R10")
      (value "49R9")
      (footprint "RESC1608X55N")
      (description "Resistor - 1%")
      (fields
        (field (name "TOLERANCE") "±1%")
        (field (name "PART NUMBER") "R0603_49R9_1%_0.1W_100PPM")
        (field (name "POWER") "0.1W")
        (field (name "AUTHOR") "CERN DEM JLC")
      )
      (libsource (lib "Resistors") (part "Resistor - 1%"))
    )
    (comp (ref "R11")
      (value "49R9")
      (footprint "RESC1608X55N")
      (description "Resistor - 1%")
      (fields
        (field (name "TOLERANCE") "±1%")
        (field (name "PART NUMBER") "R0603_49R9_1%_0.1W_100PPM")
        (field (name "POWER") "0.1W")
        (field (name "AUTHOR") "CERN DEM JLC")
      )
      (libsource (lib "Resistors") (part "Resistor - 1%"))
    )
    (comp (ref "R12")
      (value "49R9")
      (footprint "RESC1608X55N")
      (description "Resistor - 1%")
      (fields
        (field (name "TOLERANCE") "±1%")
        (field (name "PART NUMBER") "R0603_49R9_1%_0.1W_100PPM")
        (field (name "POWER") "0.1W")
        (field (name "AUTHOR") "CERN DEM JLC")
      )
      (libsource (lib "Resistors") (part "Resistor - 1%"))
    )
    (comp (ref "R13")
      (value "49R9")
      (footprint "RESC1608X55N")
      (description "Resistor - 1%")
      (fields
        (field (name "TOLERANCE") "±1%")
        (field (name "PART NUMBER") "R0603_49R9_1%_0.1W_100PPM")
        (field (name "POWER") "0.1W")
        (field (name "AUTHOR") "CERN DEM JLC")
      )
      (libsource (lib "Resistors") (part "Resistor - 1%"))
    )
    (comp (ref "R14")
      (value "49R9")
      (footprint "RESC1608X55N")
      (description "Resistor - 1%")
      (fields
        (field (name "TOLERANCE") "±1%")
        (field (name "PART NUMBER") "R0603_49R9_1%_0.1W_100PPM")
        (field (name "POWER") "0.1W")
        (field (name "AUTHOR") "CERN DEM JLC")
      )
      (libsource (lib "Resistors") (part "Resistor - 1%"))
    )
    (comp (ref "R15")
      (value "49R9")
      (footprint "RESC1608X55N")
      (description "Resistor - 1%")
      (fields
        (field (name "TOLERANCE") "±1%")
        (field (name "PART NUMBER") "R0603_49R9_1%_0.1W_100PPM")
        (field (name "POWER") "0.1W")
        (field (name "AUTHOR") "CERN DEM JLC")
      )
      (libsource (lib "Resistors") (part "Resistor - 1%"))
    )
    (comp (ref "R16")
      (value "49R9")
      (footprint "RESC1608X55N")
      (description "Resistor - 1%")
      (fields
        (field (name "TOLERANCE") "±1%")
        (field (name "PART NUMBER") "R0603_49R9_1%_0.1W_100PPM")
        (field (name "POWER") "0.1W")
        (field (name "AUTHOR") "CERN DEM JLC")
      )
      (libsource (lib "Resistors") (part "Resistor - 1%"))
    )
    (comp (ref "R17")
      (value "10k")
      (footprint "RESC1005X40N")
      (description "Resistor - 1%")
      (fields
        (field (name "TOLERANCE") "±1%")
        (field (name "PART NUMBER") "R0402_10K_1%_0.0625W_100PPM")
        (field (name "POWER") "0.0625W")
        (field (name "AUTHOR") "CERN DEM JLC")
      )
      (libsource (lib "Resistors") (part "Resistor - 1%"))
    )
    (comp (ref "R18")
      (value "10k")
      (footprint "RESC1005X40N")
      (description "Resistor - 1%")
      (fields
        (field (name "TOLERANCE") "±1%")
        (field (name "PART NUMBER") "R0402_10K_1%_0.0625W_100PPM")
        (field (name "POWER") "0.0625W")
        (field (name "AUTHOR") "CERN DEM JLC")
      )
      (libsource (lib "Resistors") (part "Resistor - 1%"))
    )
    (comp (ref "R19")
      (value "10k")
      (footprint "RESC1005X40N")
      (description "Resistor - 1%")
      (fields
        (field (name "TOLERANCE") "±1%")
        (field (name "PART NUMBER") "R0402_10K_1%_0.0625W_100PPM")
        (field (name "POWER") "0.0625W")
        (field (name "AUTHOR") "CERN DEM JLC")
      )
      (libsource (lib "Resistors") (part "Resistor - 1%"))
    )
    (comp (ref "R20")
      (value "10k")
      (footprint "RESC1005X40N")
      (description "Resistor - 1%")
      (fields
        (field (name "TOLERANCE") "±1%")
        (field (name "PART NUMBER") "R0402_10K_1%_0.0625W_100PPM")
        (field (name "POWER") "0.0625W")
        (field (name "AUTHOR") "CERN DEM JLC")
      )
      (libsource (lib "Resistors") (part "Resistor - 1%"))
    )
    (comp (ref "R21")
      (value "49R9")
      (footprint "RESC1608X55N")
      (description "Resistor - 1%")
      (fields
        (field (name "TOLERANCE") "±1%")
        (field (name "PART NUMBER") "R0603_49R9_1%_0.1W_100PPM")
        (field (name "POWER") "0.1W")
        (field (name "AUTHOR") "CERN DEM JLC")
      )
      (libsource (lib "Resistors") (part "Resistor - 1%"))
    )
    (comp (ref "R22")
      (value "49R9")
      (footprint "RESC1608X55N")
      (description "Resistor - 1%")
      (fields
        (field (name "TOLERANCE") "±1%")
        (field (name "PART NUMBER") "R0603_49R9_1%_0.1W_100PPM")
        (field (name "POWER") "0.1W")
        (field (name "AUTHOR") "CERN DEM JLC")
      )
      (libsource (lib "Resistors") (part "Resistor - 1%"))
    )
    (comp (ref "R23")
      (value "49R9")
      (footprint "RESC1608X55N")
      (description "Resistor - 1%")
      (fields
        (field (name "TOLERANCE") "±1%")
        (field (name "PART NUMBER") "R0603_49R9_1%_0.1W_100PPM")
        (field (name "POWER") "0.1W")
        (field (name "AUTHOR") "CERN DEM JLC")
      )
      (libsource (lib "Resistors") (part "Resistor - 1%"))
    )
    (comp (ref "R24")
      (value "49R9")
      (footprint "RESC1608X55N")
      (description "Resistor - 1%")
      (fields
        (field (name "TOLERANCE") "±1%")
        (field (name "PART NUMBER") "R0603_49R9_1%_0.1W_100PPM")
        (field (name "POWER") "0.1W")
        (field (name "AUTHOR") "CERN DEM JLC")
      )
      (libsource (lib "Resistors") (part "Resistor - 1%"))
    )
    (comp (ref "R25")
      (value "49R9")
      (footprint "RESC1608X55N")
      (description "Resistor - 1%")
      (fields
        (field (name "TOLERANCE") "±1%")
        (field (name "PART NUMBER") "R0603_49R9_1%_0.1W_100PPM")
        (field (name "POWER") "0.1W")
        (field (name "AUTHOR") "CERN DEM JLC")
      )
      (libsource (lib "Resistors") (part "Resistor - 1%"))
    )
    (comp (ref "R26")
      (value "49R9")
      (footprint "RESC1608X55N")
      (description "Resistor - 1%")
      (fields
        (field (name "TOLERANCE") "±1%")
        (field (name "PART NUMBER") "R0603_49R9_1%_0.1W_100PPM")
        (field (name "POWER") "0.1W")
        (field (name "AUTHOR") "CERN DEM JLC")
      )
      (libsource (lib "Resistors") (part "Resistor - 1%"))
    )
    (comp (ref "R27")
      (value "49R9")
      (footprint "RESC1608X55N")
      (description "Resistor - 1%")
      (fields
        (field (name "TOLERANCE") "±1%")
        (field (name "PART NUMBER") "R0603_49R9_1%_0.1W_100PPM")
        (field (name "POWER") "0.1W")
        (field (name "AUTHOR") "CERN DEM JLC")
      )
      (libsource (lib "Resistors") (part "Resistor - 1%"))
    )
    (comp (ref "R28")
      (value "49R9")
      (footprint "RESC1608X55N")
      (description "Resistor - 1%")
      (fields
        (field (name "TOLERANCE") "±1%")
        (field (name "PART NUMBER") "R0603_49R9_1%_0.1W_100PPM")
        (field (name "POWER") "0.1W")
        (field (name "AUTHOR") "CERN DEM JLC")
      )
      (libsource (lib "Resistors") (part "Resistor - 1%"))
    )
    (comp (ref "R29")
      (value "49R9")
      (footprint "RESC1608X55N")
      (description "Resistor - 1%")
      (fields
        (field (name "TOLERANCE") "±1%")
        (field (name "PART NUMBER") "R0603_49R9_1%_0.1W_100PPM")
        (field (name "POWER") "0.1W")
        (field (name "AUTHOR") "CERN DEM JLC")
      )
      (libsource (lib "Resistors") (part "Resistor - 1%"))
    )
    (comp (ref "R30")
      (value "49R9")
      (footprint "RESC1608X55N")
      (description "Resistor - 1%")
      (fields
        (field (name "TOLERANCE") "±1%")
        (field (name "PART NUMBER") "R0603_49R9_1%_0.1W_100PPM")
        (field (name "POWER") "0.1W")
        (field (name "AUTHOR") "CERN DEM JLC")
      )
      (libsource (lib "Resistors") (part "Resistor - 1%"))
    )
    (comp (ref "R31")
      (value "49R9")
      (footprint "RESC1608X55N")
      (description "Resistor - 1%")
      (fields
        (field (name "TOLERANCE") "±1%")
        (field (name "PART NUMBER") "R0603_49R9_1%_0.1W_100PPM")
        (field (name "POWER") "0.1W")
        (field (name "AUTHOR") "CERN DEM JLC")
      )
      (libsource (lib "Resistors") (part "Resistor - 1%"))
    )
    (comp (ref "R32")
      (value "49R9")
      (footprint "RESC1608X55N")
      (description "Resistor - 1%")
      (fields
        (field (name "TOLERANCE") "±1%")
        (field (name "PART NUMBER") "R0603_49R9_1%_0.1W_100PPM")
        (field (name "POWER") "0.1W")
        (field (name "AUTHOR") "CERN DEM JLC")
      )
      (libsource (lib "Resistors") (part "Resistor - 1%"))
    )
    (comp (ref "R33")
      (value "49R9")
      (footprint "RESC1608X55N")
      (description "Resistor - 1%")
      (fields
        (field (name "TOLERANCE") "±1%")
        (field (name "PART NUMBER") "R0603_49R9_1%_0.1W_100PPM")
        (field (name "POWER") "0.1W")
        (field (name "AUTHOR") "CERN DEM JLC")
      )
      (libsource (lib "Resistors") (part "Resistor - 1%"))
    )
    (comp (ref "R34")
      (value "49R9")
      (footprint "RESC1608X55N")
      (description "Resistor - 1%")
      (fields
        (field (name "TOLERANCE") "±1%")
        (field (name "PART NUMBER") "R0603_49R9_1%_0.1W_100PPM")
        (field (name "POWER") "0.1W")
        (field (name "AUTHOR") "CERN DEM JLC")
      )
      (libsource (lib "Resistors") (part "Resistor - 1%"))
    )
    (comp (ref "R35")
      (value "49R9")
      (footprint "RESC1608X55N")
      (description "Resistor - 1%")
      (fields
        (field (name "TOLERANCE") "±1%")
        (field (name "PART NUMBER") "R0603_49R9_1%_0.1W_100PPM")
        (field (name "POWER") "0.1W")
        (field (name "AUTHOR") "CERN DEM JLC")
      )
      (libsource (lib "Resistors") (part "Resistor - 1%"))
    )
    (comp (ref "R36")
      (value "49R9")
      (footprint "RESC1608X55N")
      (description "Resistor - 1%")
      (fields
        (field (name "TOLERANCE") "±1%")
        (field (name "PART NUMBER") "R0603_49R9_1%_0.1W_100PPM")
        (field (name "POWER") "0.1W")
        (field (name "AUTHOR") "CERN DEM JLC")
      )
      (libsource (lib "Resistors") (part "Resistor - 1%"))
    )
  )
  (nets
    (net (code "1") (name "+3V3") (class "Default")
      (node (ref "C33") (pin "1") (pinfunction "1_1") (pintype "passive"))
      (node (ref "C34") (pin "1") (pinfunction "1_1") (pintype "passive"))
      (node (ref "C69") (pin "2") (pinfunction "2_2") (pintype "passive"))
      (node (ref "IC2") (pin "4") (pinfunction "VCC_4") (pintype "power_in"))
      (node (ref "J1") (pin "39") (pinfunction "39_39") (pintype "passive"))
      (node (ref "J1") (pin "40") (pinfunction "40_40") (pintype "passive"))
      (node (ref "R17") (pin "2") (pinfunction "2_2") (pintype "passive"))
      (node (ref "R18") (pin "2") (pinfunction "2_2") (pintype "passive"))
      (node (ref "R19") (pin "2") (pinfunction "2_2") (pintype "passive"))
      (node (ref "R20") (pin "2") (pinfunction "2_2") (pintype "passive"))
    )
    (net (code "2") (name "/ID0{slash}SDA") (class "Default")
      (node (ref "IC2") (pin "3") (pinfunction "SDA_3") (pintype "bidirectional"))
      (node (ref "J1") (pin "36") (pinfunction "36_36") (pintype "passive"))
      (node (ref "R18") (pin "1") (pinfunction "1_1") (pintype "passive"))
    )
    (net (code "3") (name "/ID1{slash}SCL") (class "Default")
      (node (ref "IC2") (pin "1") (pinfunction "SCL_1") (pintype "input"))
      (node (ref "J1") (pin "38") (pinfunction "38_38") (pintype "passive"))
      (node (ref "R17") (pin "1") (pinfunction "1_1") (pintype "passive"))
    )
    (net (code "4") (name "/ID2") (class "Default")
      (node (ref "J1") (pin "35") (pinfunction "35_35") (pintype "passive"))
      (node (ref "R19") (pin "1") (pinfunction "1_1") (pintype "passive"))
    )
    (net (code "5") (name "/ID3") (class "Default")
      (node (ref "J1") (pin "37") (pinfunction "37_37") (pintype "passive"))
      (node (ref "R20") (pin "1") (pinfunction "1_1") (pintype "passive"))
    )
    (net (code "6") (name "/IN0_FASTIC1") (class "Default")
      (node (ref "IC1") (pin "1") (pinfunction "A_1") (pintype "passive"))
      (node (ref "J1") (pin "32") (pinfunction "32_32") (pintype "passive"))
    )
    (net (code "7") (name "/IN0_FASTIC2") (class "Default")
      (node (ref "IC3") (pin "1") (pinfunction "A_1") (pintype "passive"))
      (node (ref "J1") (pin "11") (pinfunction "11_11") (pintype "passive"))
    )
    (net (code "8") (name "/IN1_FASTIC1") (class "Default")
      (node (ref "IC4") (pin "1") (pinfunction "A_1") (pintype "passive"))
      (node (ref "J1") (pin "30") (pinfunction "30_30") (pintype "passive"))
    )
    (net (code "9") (name "/IN1_FASTIC2") (class "Default")
      (node (ref "IC5") (pin "1") (pinfunction "A_1") (pintype "passive"))
      (node (ref "J1") (pin "13") (pinfunction "13_13") (pintype "passive"))
    )
    (net (code "10") (name "/IN2_FASTIC1") (class "Default")
      (node (ref "IC6") (pin "1") (pinfunction "A_1") (pintype "passive"))
      (node (ref "J1") (pin "26") (pinfunction "26_26") (pintype "passive"))
    )
    (net (code "11") (name "/IN2_FASTIC2") (class "Default")
      (node (ref "IC7") (pin "1") (pinfunction "A_1") (pintype "passive"))
      (node (ref "J1") (pin "17") (pinfunction "17_17") (pintype "passive"))
    )
    (net (code "12") (name "/IN3_FASTIC1") (class "Default")
      (node (ref "IC8") (pin "1") (pinfunction "A_1") (pintype "passive"))
      (node (ref "J1") (pin "24") (pinfunction "24_24") (pintype "passive"))
    )
    (net (code "13") (name "/IN3_FASTIC2") (class "Default")
      (node (ref "IC9") (pin "1") (pinfunction "A_1") (pintype "passive"))
      (node (ref "J1") (pin "19") (pinfunction "19_19") (pintype "passive"))
    )
    (net (code "14") (name "/IN4_FASTIC1") (class "Default")
      (node (ref "IC10") (pin "1") (pinfunction "A_1") (pintype "passive"))
      (node (ref "J1") (pin "20") (pinfunction "20_20") (pintype "passive"))
    )
    (net (code "15") (name "/IN4_FASTIC2") (class "Default")
      (node (ref "IC11") (pin "1") (pinfunction "A_1") (pintype "passive"))
      (node (ref "J1") (pin "23") (pinfunction "23_23") (pintype "passive"))
    )
    (net (code "16") (name "/IN5_FASTIC1") (class "Default")
      (node (ref "IC12") (pin "1") (pinfunction "A_1") (pintype "passive"))
      (node (ref "J1") (pin "18") (pinfunction "18_18") (pintype "passive"))
    )
    (net (code "17") (name "/IN5_FASTIC2") (class "Default")
      (node (ref "IC13") (pin "1") (pinfunction "A_1") (pintype "passive"))
      (node (ref "J1") (pin "25") (pinfunction "25_25") (pintype "passive"))
    )
    (net (code "18") (name "/IN6_FASTIC1") (class "Default")
      (node (ref "IC14") (pin "1") (pinfunction "A_1") (pintype "passive"))
      (node (ref "J1") (pin "14") (pinfunction "14_14") (pintype "passive"))
    )
    (net (code "19") (name "/IN6_FASTIC2") (class "Default")
      (node (ref "IC15") (pin "1") (pinfunction "A_1") (pintype "passive"))
      (node (ref "J1") (pin "29") (pinfunction "29_29") (pintype "passive"))
    )
    (net (code "20") (name "/IN7_FASTIC1") (class "Default")
      (node (ref "IC16") (pin "1") (pinfunction "A_1") (pintype "passive"))
      (node (ref "J1") (pin "12") (pinfunction "12_12") (pintype "passive"))
    )
    (net (code "21") (name "/IN7_FASTIC2") (class "Default")
      (node (ref "IC17") (pin "1") (pinfunction "A_1") (pintype "passive"))
      (node (ref "J1") (pin "31") (pinfunction "31_31") (pintype "passive"))
    )
    (net (code "22") (name "GND") (class "Default")
      (node (ref "C1") (pin "1") (pinfunction "1_1") (pintype "passive"))
      (node (ref "C10") (pin "1") (pinfunction "1_1") (pintype "passive"))
      (node (ref "C11") (pin "1") (pinfunction "1_1") (pintype "passive"))
      (node (ref "C12") (pin "1") (pinfunction "1_1") (pintype "passive"))
      (node (ref "C13") (pin "1") (pinfunction "1_1") (pintype "passive"))
      (node (ref "C14") (pin "1") (pinfunction "1_1") (pintype "passive"))
      (node (ref "C15") (pin "1") (pinfunction "1_1") (pintype "passive"))
      (node (ref "C16") (pin "1") (pinfunction "1_1") (pintype "passive"))
      (node (ref "C17") (pin "1") (pinfunction "1_1") (pintype "passive"))
      (node (ref "C18") (pin "1") (pinfunction "1_1") (pintype "passive"))
      (node (ref "C19") (pin "1") (pinfunction "1_1") (pintype "passive"))
      (node (ref "C2") (pin "1") (pinfunction "1_1") (pintype "passive"))
      (node (ref "C20") (pin "1") (pinfunction "1_1") (pintype "passive"))
      (node (ref "C21") (pin "1") (pinfunction "1_1") (pintype "passive"))
      (node (ref "C22") (pin "1") (pinfunction "1_1") (pintype "passive"))
      (node (ref "C23") (pin "1") (pinfunction "1_1") (pintype "passive"))
      (node (ref "C24") (pin "1") (pinfunction "1_1") (pintype "passive"))
      (node (ref "C25") (pin "1") (pinfunction "1_1") (pintype "passive"))
      (node (ref "C26") (pin "1") (pinfunction "1_1") (pintype "passive"))
      (node (ref "C27") (pin "1") (pinfunction "1_1") (pintype "passive"))
      (node (ref "C28") (pin "1") (pinfunction "1_1") (pintype "passive"))
      (node (ref "C29") (pin "1") (pinfunction "1_1") (pintype "passive"))
      (node (ref "C3") (pin "1") (pinfunction "1_1") (pintype "passive"))
      (node (ref "C30") (pin "1") (pinfunction "1_1") (pintype "passive"))
      (node (ref "C31") (pin "1") (pinfunction "1_1") (pintype "passive"))
      (node (ref "C32") (pin "1") (pinfunction "1_1") (pintype "passive"))
      (node (ref "C33") (pin "2") (pinfunction "2_2") (pintype "passive"))
      (node (ref "C34") (pin "2") (pinfunction "2_2") (pintype "passive"))
      (node (ref "C35") (pin "1") (pinfunction "1_1") (pintype "passive"))
      (node (ref "C36") (pin "1") (pinfunction "1_1") (pintype "passive"))
      (node (ref "C37") (pin "1") (pinfunction "1_1") (pintype "passive"))
      (node (ref "C38") (pin "1") (pinfunction "1_1") (pintype "passive"))
      (node (ref "C39") (pin "1") (pinfunction "1_1") (pintype "passive"))
      (node (ref "C4") (pin "1") (pinfunction "1_1") (pintype "passive"))
      (node (ref "C40") (pin "1") (pinfunction "1_1") (pintype "passive"))
      (node (ref "C41") (pin "1") (pinfunction "1_1") (pintype "passive"))
      (node (ref "C42") (pin "1") (pinfunction "1_1") (pintype "passive"))
      (node (ref "C43") (pin "1") (pinfunction "1_1") (pintype "passive"))
      (node (ref "C44") (pin "1") (pinfunction "1_1") (pintype "passive"))
      (node (ref "C45") (pin "1") (pinfunction "1_1") (pintype "passive"))
      (node (ref "C46") (pin "1") (pinfunction "1_1") (pintype "passive"))
      (node (ref "C47") (pin "1") (pinfunction "1_1") (pintype "passive"))
      (node (ref "C48") (pin "1") (pinfunction "1_1") (pintype "passive"))
      (node (ref "C49") (pin "1") (pinfunction "1_1") (pintype "passive"))
      (node (ref "C5") (pin "1") (pinfunction "1_1") (pintype "passive"))
      (node (ref "C50") (pin "1") (pinfunction "1_1") (pintype "passive"))
      (node (ref "C51") (pin "1") (pinfunction "1_1") (pintype "passive"))
      (node (ref "C52") (pin "1") (pinfunction "1_1") (pintype "passive"))
      (node (ref "C53") (pin "1") (pinfunction "1_1") (pintype "passive"))
      (node (ref "C54") (pin "1") (pinfunction "1_1") (pintype "passive"))
      (node (ref "C55") (pin "1") (pinfunction "1_1") (pintype "passive"))
      (node (ref "C56") (pin "1") (pinfunction "1_1") (pintype "passive"))
      (node (ref "C57") (pin "1") (pinfunction "1_1") (pintype "passive"))
      (node (ref "C58") (pin "1") (pinfunction "1_1") (pintype "passive"))
      (node (ref "C59") (pin "1") (pinfunction "1_1") (pintype "passive"))
      (node (ref "C6") (pin "1") (pinfunction "1_1") (pintype "passive"))
      (node (ref "C60") (pin "1") (pinfunction "1_1") (pintype "passive"))
      (node (ref "C61") (pin "1") (pinfunction "1_1") (pintype "passive"))
      (node (ref "C62") (pin "1") (pinfunction "1_1") (pintype "passive"))
      (node (ref "C63") (pin "1") (pinfunction "1_1") (pintype "passive"))
      (node (ref "C64") (pin "1") (pinfunction "1_1") (pintype "passive"))
      (node (ref "C65") (pin "1") (pinfunction "1_1") (pintype "passive"))
      (node (ref "C66") (pin "1") (pinfunction "1_1") (pintype "passive"))
      (node (ref "C67") (pin "1") (pinfunction "1_1") (pintype "passive"))
      (node (ref "C68") (pin "1") (pinfunction "1_1") (pintype "passive"))
      (node (ref "C69") (pin "1") (pinfunction "1_1") (pintype "passive"))
      (node (ref "C7") (pin "1") (pinfunction "1_1") (pintype "passive"))
      (node (ref "C8") (pin "1") (pinfunction "1_1") (pintype "passive"))
      (node (ref "C9") (pin "1") (pinfunction "1_1") (pintype "passive"))
      (node (ref "H1") (pin "1") (pinfunction "1_1") (pintype "bidirectional"))
      (node (ref "H2") (pin "1") (pinfunction "1_1") (pintype "bidirectional"))
      (node (ref "H3") (pin "1") (pinfunction "1_1") (pintype "bidirectional"))
      (node (ref "H4") (pin "1") (pinfunction "1_1") (pintype "bidirectional"))
      (node (ref "IC2") (pin "2") (pinfunction "VSS_2") (pintype "power_in"))
      (node (ref "IC2") (pin "5") (pinfunction "WP_5") (pintype "input"))
      (node (ref "J1") (pin "09") (pinfunction "09_09") (pintype "passive"))
      (node (ref "J1") (pin "10") (pinfunction "10_10") (pintype "passive"))
      (node (ref "J1") (pin "15") (pinfunction "15_15") (pintype "passive"))
      (node (ref "J1") (pin "16") (pinfunction "16_16") (pintype "passive"))
      (node (ref "J1") (pin "21") (pinfunction "21_21") (pintype "passive"))
      (node (ref "J1") (pin "22") (pinfunction "22_22") (pintype "passive"))
      (node (ref "J1") (pin "27") (pinfunction "27_27") (pintype "passive"))
      (node (ref "J1") (pin "28") (pinfunction "28_28") (pintype "passive"))
      (node (ref "J1") (pin "33") (pinfunction "33_33") (pintype "passive"))
      (node (ref "J1") (pin "34") (pinfunction "34_34") (pintype "passive"))
    )
    (net (code "23") (name "HV") (class "Default")
      (node (ref "C51") (pin "2") (pinfunction "2_2") (pintype "passive"))
      (node (ref "C52") (pin "2") (pinfunction "2_2") (pintype "passive"))
      (node (ref "J1") (pin "01") (pinfunction "01_01") (pintype "passive"))
      (node (ref "J1") (pin "02") (pinfunction "02_02") (pintype "passive"))
      (node (ref "J1") (pin "03") (pinfunction "03_03") (pintype "passive"))
      (node (ref "J1") (pin "04") (pinfunction "04_04") (pintype "passive"))
      (node (ref "R1") (pin "1") (pinfunction "1_1") (pintype "passive"))
      (node (ref "R11") (pin "1") (pinfunction "1_1") (pintype "passive"))
      (node (ref "R13") (pin "1") (pinfunction "1_1") (pintype "passive"))
      (node (ref "R15") (pin "1") (pinfunction "1_1") (pintype "passive"))
      (node (ref "R21") (pin "1") (pinfunction "1_1") (pintype "passive"))
      (node (ref "R23") (pin "1") (pinfunction "1_1") (pintype "passive"))
      (node (ref "R25") (pin "1") (pinfunction "1_1") (pintype "passive"))
      (node (ref "R27") (pin "1") (pinfunction "1_1") (pintype "passive"))
      (node (ref "R29") (pin "1") (pinfunction "1_1") (pintype "passive"))
      (node (ref "R3") (pin "1") (pinfunction "1_1") (pintype "passive"))
      (node (ref "R31") (pin "1") (pinfunction "1_1") (pintype "passive"))
      (node (ref "R33") (pin "1") (pinfunction "1_1") (pintype "passive"))
      (node (ref "R35") (pin "1") (pinfunction "1_1") (pintype "passive"))
      (node (ref "R5") (pin "1") (pinfunction "1_1") (pintype "passive"))
      (node (ref "R7") (pin "1") (pinfunction "1_1") (pintype "passive"))
      (node (ref "R9") (pin "1") (pinfunction "1_1") (pintype "passive"))
    )
    (net (code "24") (name "Net-(C1-Pad2)") (class "Default")
      (node (ref "C1") (pin "2") (pinfunction "2_2") (pintype "passive"))
      (node (ref "C2") (pin "2") (pinfunction "2_2") (pintype "passive"))
      (node (ref "R1") (pin "2") (pinfunction "2_2") (pintype "passive"))
      (node (ref "R2") (pin "1") (pinfunction "1_1") (pintype "passive"))
    )
    (net (code "25") (name "Net-(C5-Pad2)") (class "Default")
      (node (ref "C5") (pin "2") (pinfunction "2_2") (pintype "passive"))
      (node (ref "C6") (pin "2") (pinfunction "2_2") (pintype "passive"))
      (node (ref "R3") (pin "2") (pinfunction "2_2") (pintype "passive"))
      (node (ref "R4") (pin "1") (pinfunction "1_1") (pintype "passive"))
    )
    (net (code "26") (name "Net-(C10-Pad2)") (class "Default")
      (node (ref "C10") (pin "2") (pinfunction "2_2") (pintype "passive"))
      (node (ref "C9") (pin "2") (pinfunction "2_2") (pintype "passive"))
      (node (ref "R5") (pin "2") (pinfunction "2_2") (pintype "passive"))
      (node (ref "R6") (pin "1") (pinfunction "1_1") (pintype "passive"))
    )
    (net (code "27") (name "Net-(C13-Pad2)") (class "Default")
      (node (ref "C13") (pin "2") (pinfunction "2_2") (pintype "passive"))
      (node (ref "C14") (pin "2") (pinfunction "2_2") (pintype "passive"))
      (node (ref "R7") (pin "2") (pinfunction "2_2") (pintype "passive"))
      (node (ref "R8") (pin "1") (pinfunction "1_1") (pintype "passive"))
    )
    (net (code "28") (name "Net-(C17-Pad2)") (class "Default")
      (node (ref "C17") (pin "2") (pinfunction "2_2") (pintype "passive"))
      (node (ref "C18") (pin "2") (pinfunction "2_2") (pintype "passive"))
      (node (ref "R10") (pin "1") (pinfunction "1_1") (pintype "passive"))
      (node (ref "R9") (pin "2") (pinfunction "2_2") (pintype "passive"))
    )
    (net (code "29") (name "Net-(C21-Pad2)") (class "Default")
      (node (ref "C21") (pin "2") (pinfunction "2_2") (pintype "passive"))
      (node (ref "C22") (pin "2") (pinfunction "2_2") (pintype "passive"))
      (node (ref "R11") (pin "2") (pinfunction "2_2") (pintype "passive"))
      (node (ref "R12") (pin "1") (pinfunction "1_1") (pintype "passive"))
    )
    (net (code "30") (name "Net-(C25-Pad2)") (class "Default")
      (node (ref "C25") (pin "2") (pinfunction "2_2") (pintype "passive"))
      (node (ref "C26") (pin "2") (pinfunction "2_2") (pintype "passive"))
      (node (ref "R13") (pin "2") (pinfunction "2_2") (pintype "passive"))
      (node (ref "R14") (pin "1") (pinfunction "1_1") (pintype "passive"))
    )
    (net (code "31") (name "Net-(C29-Pad2)") (class "Default")
      (node (ref "C29") (pin "2") (pinfunction "2_2") (pintype "passive"))
      (node (ref "C30") (pin "2") (pinfunction "2_2") (pintype "passive"))
      (node (ref "R15") (pin "2") (pinfunction "2_2") (pintype "passive"))
      (node (ref "R16") (pin "1") (pinfunction "1_1") (pintype "passive"))
    )
    (net (code "32") (name "Net-(C35-Pad2)") (class "Default")
      (node (ref "C35") (pin "2") (pinfunction "2_2") (pintype "passive"))
      (node (ref "C36") (pin "2") (pinfunction "2_2") (pintype "passive"))
      (node (ref "R21") (pin "2") (pinfunction "2_2") (pintype "passive"))
      (node (ref "R22") (pin "1") (pinfunction "1_1") (pintype "passive"))
    )
    (net (code "33") (name "Net-(C39-Pad2)") (class "Default")
      (node (ref "C39") (pin "2") (pinfunction "2_2") (pintype "passive"))
      (node (ref "C40") (pin "2") (pinfunction "2_2") (pintype "passive"))
      (node (ref "R23") (pin "2") (pinfunction "2_2") (pintype "passive"))
      (node (ref "R24") (pin "1") (pinfunction "1_1") (pintype "passive"))
    )
    (net (code "34") (name "Net-(C43-Pad2)") (class "Default")
      (node (ref "C43") (pin "2") (pinfunction "2_2") (pintype "passive"))
      (node (ref "C44") (pin "2") (pinfunction "2_2") (pintype "passive"))
      (node (ref "R25") (pin "2") (pinfunction "2_2") (pintype "passive"))
      (node (ref "R26") (pin "1") (pinfunction "1_1") (pintype "passive"))
    )
    (net (code "35") (name "Net-(C47-Pad2)") (class "Default")
      (node (ref "C47") (pin "2") (pinfunction "2_2") (pintype "passive"))
      (node (ref "C48") (pin "2") (pinfunction "2_2") (pintype "passive"))
      (node (ref "R27") (pin "2") (pinfunction "2_2") (pintype "passive"))
      (node (ref "R28") (pin "1") (pinfunction "1_1") (pintype "passive"))
    )
    (net (code "36") (name "Net-(C53-Pad2)") (class "Default")
      (node (ref "C53") (pin "2") (pinfunction "2_2") (pintype "passive"))
      (node (ref "C54") (pin "2") (pinfunction "2_2") (pintype "passive"))
      (node (ref "R29") (pin "2") (pinfunction "2_2") (pintype "passive"))
      (node (ref "R30") (pin "1") (pinfunction "1_1") (pintype "passive"))
    )
    (net (code "37") (name "Net-(C57-Pad2)") (class "Default")
      (node (ref "C57") (pin "2") (pinfunction "2_2") (pintype "passive"))
      (node (ref "C58") (pin "2") (pinfunction "2_2") (pintype "passive"))
      (node (ref "R31") (pin "2") (pinfunction "2_2") (pintype "passive"))
      (node (ref "R32") (pin "1") (pinfunction "1_1") (pintype "passive"))
    )
    (net (code "38") (name "Net-(C61-Pad2)") (class "Default")
      (node (ref "C61") (pin "2") (pinfunction "2_2") (pintype "passive"))
      (node (ref "C62") (pin "2") (pinfunction "2_2") (pintype "passive"))
      (node (ref "R33") (pin "2") (pinfunction "2_2") (pintype "passive"))
      (node (ref "R34") (pin "1") (pinfunction "1_1") (pintype "passive"))
    )
    (net (code "39") (name "Net-(C65-Pad2)") (class "Default")
      (node (ref "C65") (pin "2") (pinfunction "2_2") (pintype "passive"))
      (node (ref "C66") (pin "2") (pinfunction "2_2") (pintype "passive"))
      (node (ref "R35") (pin "2") (pinfunction "2_2") (pintype "passive"))
      (node (ref "R36") (pin "1") (pinfunction "1_1") (pintype "passive"))
    )
    (net (code "40") (name "Net-(IC1-C)") (class "Default")
      (node (ref "C3") (pin "2") (pinfunction "2_2") (pintype "passive"))
      (node (ref "C4") (pin "2") (pinfunction "2_2") (pintype "passive"))
      (node (ref "IC1") (pin "2") (pinfunction "C_2") (pintype "passive"))
      (node (ref "R2") (pin "2") (pinfunction "2_2") (pintype "passive"))
    )
    (net (code "41") (name "Net-(IC3-C)") (class "Default")
      (node (ref "C7") (pin "2") (pinfunction "2_2") (pintype "passive"))
      (node (ref "C8") (pin "2") (pinfunction "2_2") (pintype "passive"))
      (node (ref "IC3") (pin "2") (pinfunction "C_2") (pintype "passive"))
      (node (ref "R4") (pin "2") (pinfunction "2_2") (pintype "passive"))
    )
    (net (code "42") (name "Net-(IC4-C)") (class "Default")
      (node (ref "C11") (pin "2") (pinfunction "2_2") (pintype "passive"))
      (node (ref "C12") (pin "2") (pinfunction "2_2") (pintype "passive"))
      (node (ref "IC4") (pin "2") (pinfunction "C_2") (pintype "passive"))
      (node (ref "R6") (pin "2") (pinfunction "2_2") (pintype "passive"))
    )
    (net (code "43") (name "Net-(IC5-C)") (class "Default")
      (node (ref "C15") (pin "2") (pinfunction "2_2") (pintype "passive"))
      (node (ref "C16") (pin "2") (pinfunction "2_2") (pintype "passive"))
      (node (ref "IC5") (pin "2") (pinfunction "C_2") (pintype "passive"))
      (node (ref "R8") (pin "2") (pinfunction "2_2") (pintype "passive"))
    )
    (net (code "44") (name "Net-(IC6-C)") (class "Default")
      (node (ref "C19") (pin "2") (pinfunction "2_2") (pintype "passive"))
      (node (ref "C20") (pin "2") (pinfunction "2_2") (pintype "passive"))
      (node (ref "IC6") (pin "2") (pinfunction "C_2") (pintype "passive"))
      (node (ref "R10") (pin "2") (pinfunction "2_2") (pintype "passive"))
    )
    (net (code "45") (name "Net-(IC7-C)") (class "Default")
      (node (ref "C23") (pin "2") (pinfunction "2_2") (pintype "passive"))
      (node (ref "C24") (pin "2") (pinfunction "2_2") (pintype "passive"))
      (node (ref "IC7") (pin "2") (pinfunction "C_2") (pintype "passive"))
      (node (ref "R12") (pin "2") (pinfunction "2_2") (pintype "passive"))
    )
    (net (code "46") (name "Net-(IC8-C)") (class "Default")
      (node (ref "C27") (pin "2") (pinfunction "2_2") (pintype "passive"))
      (node (ref "C28") (pin "2") (pinfunction "2_2") (pintype "passive"))
      (node (ref "IC8") (pin "2") (pinfunction "C_2") (pintype "passive"))
      (node (ref "R14") (pin "2") (pinfunction "2_2") (pintype "passive"))
    )
    (net (code "47") (name "Net-(IC9-C)") (class "Default")
      (node (ref "C31") (pin "2") (pinfunction "2_2") (pintype "passive"))
      (node (ref "C32") (pin "2") (pinfunction "2_2") (pintype "passive"))
      (node (ref "IC9") (pin "2") (pinfunction "C_2") (pintype "passive"))
      (node (ref "R16") (pin "2") (pinfunction "2_2") (pintype "passive"))
    )
    (net (code "48") (name "Net-(IC10-C)") (class "Default")
      (node (ref "C37") (pin "2") (pinfunction "2_2") (pintype "passive"))
      (node (ref "C38") (pin "2") (pinfunction "2_2") (pintype "passive"))
      (node (ref "IC10") (pin "2") (pinfunction "C_2") (pintype "passive"))
      (node (ref "R22") (pin "2") (pinfunction "2_2") (pintype "passive"))
    )
    (net (code "49") (name "Net-(IC11-C)") (class "Default")
      (node (ref "C41") (pin "2") (pinfunction "2_2") (pintype "passive"))
      (node (ref "C42") (pin "2") (pinfunction "2_2") (pintype "passive"))
      (node (ref "IC11") (pin "2") (pinfunction "C_2") (pintype "passive"))
      (node (ref "R24") (pin "2") (pinfunction "2_2") (pintype "passive"))
    )
    (net (code "50") (name "Net-(IC12-C)") (class "Default")
      (node (ref "C45") (pin "2") (pinfunction "2_2") (pintype "passive"))
      (node (ref "C46") (pin "2") (pinfunction "2_2") (pintype "passive"))
      (node (ref "IC12") (pin "2") (pinfunction "C_2") (pintype "passive"))
      (node (ref "R26") (pin "2") (pinfunction "2_2") (pintype "passive"))
    )
    (net (code "51") (name "Net-(IC13-C)") (class "Default")
      (node (ref "C49") (pin "2") (pinfunction "2_2") (pintype "passive"))
      (node (ref "C50") (pin "2") (pinfunction "2_2") (pintype "passive"))
      (node (ref "IC13") (pin "2") (pinfunction "C_2") (pintype "passive"))
      (node (ref "R28") (pin "2") (pinfunction "2_2") (pintype "passive"))
    )
    (net (code "52") (name "Net-(IC14-C)") (class "Default")
      (node (ref "C55") (pin "2") (pinfunction "2_2") (pintype "passive"))
      (node (ref "C56") (pin "2") (pinfunction "2_2") (pintype "passive"))
      (node (ref "IC14") (pin "2") (pinfunction "C_2") (pintype "passive"))
      (node (ref "R30") (pin "2") (pinfunction "2_2") (pintype "passive"))
    )
    (net (code "53") (name "Net-(IC15-C)") (class "Default")
      (node (ref "C59") (pin "2") (pinfunction "2_2") (pintype "passive"))
      (node (ref "C60") (pin "2") (pinfunction "2_2") (pintype "passive"))
      (node (ref "IC15") (pin "2") (pinfunction "C_2") (pintype "passive"))
      (node (ref "R32") (pin "2") (pinfunction "2_2") (pintype "passive"))
    )
    (net (code "54") (name "Net-(IC16-C)") (class "Default")
      (node (ref "C63") (pin "2") (pinfunction "2_2") (pintype "passive"))
      (node (ref "C64") (pin "2") (pinfunction "2_2") (pintype "passive"))
      (node (ref "IC16") (pin "2") (pinfunction "C_2") (pintype "passive"))
      (node (ref "R34") (pin "2") (pinfunction "2_2") (pintype "passive"))
    )
    (net (code "55") (name "Net-(IC17-C)") (class "Default")
      (node (ref "C67") (pin "2") (pinfunction "2_2") (pintype "passive"))
      (node (ref "C68") (pin "2") (pinfunction "2_2") (pintype "passive"))
      (node (ref "IC17") (pin "2") (pinfunction "C_2") (pintype "passive"))
      (node (ref "R36") (pin "2") (pinfunction "2_2") (pintype "passive"))
    )
    (net (code "56") (name "unconnected-(J1-Pad05)") (class "Default")
      (node (ref "J1") (pin "05") (pinfunction "05_05") (pintype "passive+no_connect"))
    )
    (net (code "57") (name "unconnected-(J1-Pad06)") (class "Default")
      (node (ref "J1") (pin "06") (pinfunction "06_06") (pintype "passive+no_connect"))
    )
    (net (code "58") (name "unconnected-(J1-Pad07)") (class "Default")
      (node (ref "J1") (pin "07") (pinfunction "07_07") (pintype "passive+no_connect"))
    )
    (net (code "59") (name "unconnected-(J1-Pad08)") (class "Default")
      (node (ref "J1") (pin "08") (pinfunction "08_08") (pintype "passive+no_connect"))
    )
  )
)
